# SparkFun_QwiicBus_Endpoint.net
KiCad netlist of a schematic drawn in EAGLE
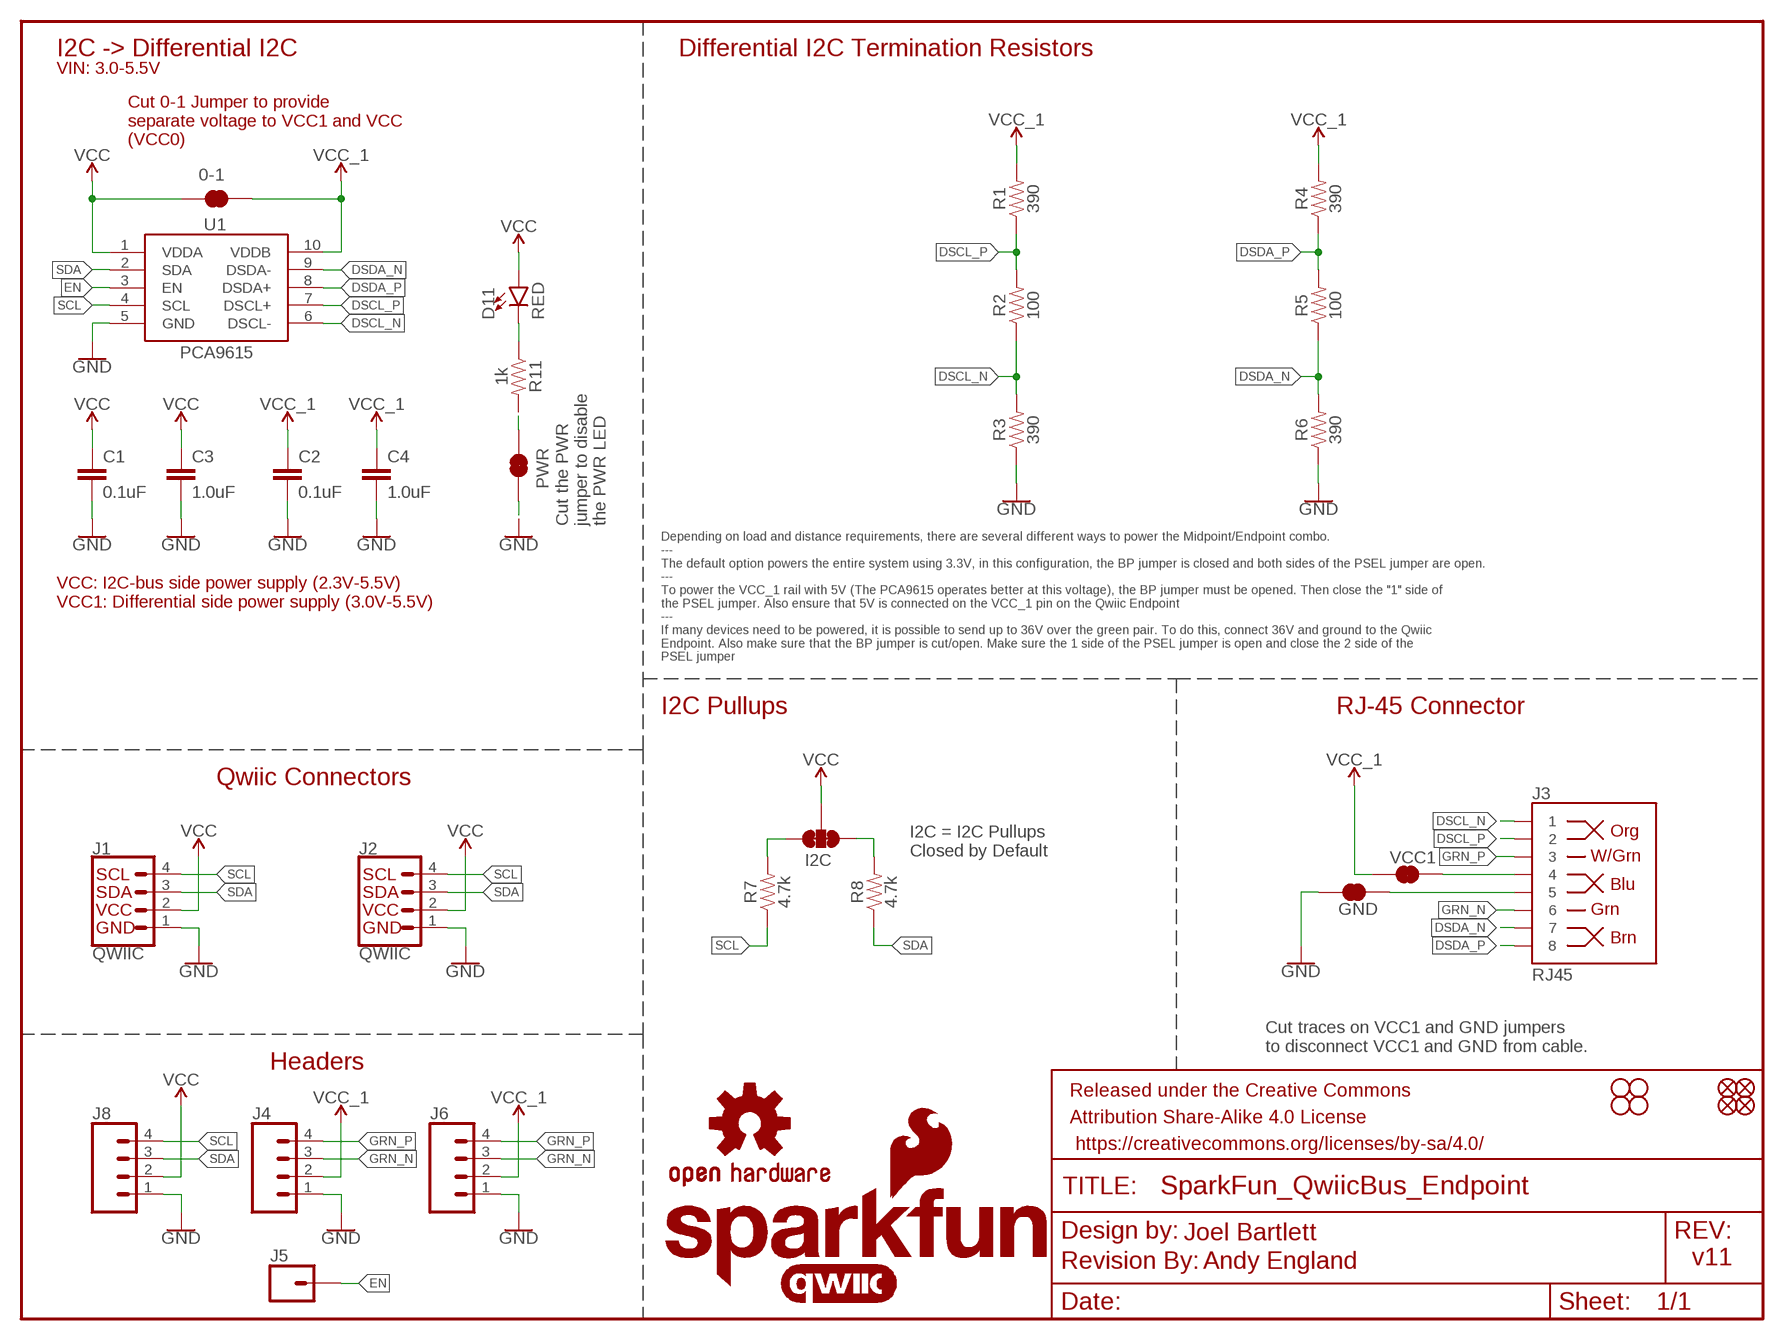
[diagram p0: schematic, sheet 1]

(export (version "E")
  (design (tool "Eeschema 10.0.6"))
  (components
    (comp (ref "0-1")
      (value "JUMPER-SMT_2_NC_TRACE_SILK")
      (footprint "eagle-import:SMT-JUMPER_2_NC_TRACE_SILK")
      (libsource (lib "eagle-import") (part "JUMPER-SMT_2_NC_TRACE_SILK"))
    )
    (comp (ref "C1")
      (value "0.1uF")
      (footprint "eagle-import:0603")
      (libsource (lib "eagle-import") (part "0.1UF-0603-25V-(+80/-20%)"))
    )
    (comp (ref "C2")
      (value "0.1uF")
      (footprint "eagle-import:0603")
      (libsource (lib "eagle-import") (part "0.1UF-0603-25V-(+80/-20%)"))
    )
    (comp (ref "C3")
      (value "1.0uF")
      (footprint "eagle-import:0603")
      (libsource (lib "eagle-import") (part "1.0UF-0603-16V-10%"))
    )
    (comp (ref "C4")
      (value "1.0uF")
      (footprint "eagle-import:0603")
      (libsource (lib "eagle-import") (part "1.0UF-0603-16V-10%"))
    )
    (comp (ref "D11")
      (value "RED")
      (footprint "eagle-import:LED-0603")
      (libsource (lib "eagle-import") (part "LED-RED0603"))
    )
    (comp (ref "FD1")
      (value "FIDUCIALUFIDUCIAL")
      (footprint "eagle-import:FIDUCIAL-MICRO")
      (libsource (lib "eagle-import") (part "FIDUCIALUFIDUCIAL"))
    )
    (comp (ref "FD2")
      (value "FIDUCIALUFIDUCIAL")
      (footprint "eagle-import:FIDUCIAL-MICRO")
      (libsource (lib "eagle-import") (part "FIDUCIALUFIDUCIAL"))
    )
    (comp (ref "FD3")
      (value "FIDUCIALUFIDUCIAL")
      (footprint "eagle-import:FIDUCIAL-MICRO")
      (libsource (lib "eagle-import") (part "FIDUCIALUFIDUCIAL"))
    )
    (comp (ref "FD4")
      (value "FIDUCIALUFIDUCIAL")
      (footprint "eagle-import:FIDUCIAL-MICRO")
      (libsource (lib "eagle-import") (part "FIDUCIALUFIDUCIAL"))
    )
    (comp (ref "FRAME1")
      (value "FRAME-LETTER")
      (footprint "eagle-import:CREATIVE_COMMONS")
      (libsource (lib "eagle-import") (part "FRAME-LETTER"))
    )
    (comp (ref "GND")
      (value "JUMPER-SMT_2_NC_TRACE_SILK")
      (footprint "eagle-import:SMT-JUMPER_2_NC_TRACE_SILK")
      (libsource (lib "eagle-import") (part "JUMPER-SMT_2_NC_TRACE_SILK"))
    )
    (comp (ref "H1")
      (value "STAND-OFF")
      (footprint "eagle-import:STAND-OFF")
      (libsource (lib "eagle-import") (part "STAND-OFF"))
    )
    (comp (ref "H2")
      (value "STAND-OFF")
      (footprint "eagle-import:STAND-OFF")
      (libsource (lib "eagle-import") (part "STAND-OFF"))
    )
    (comp (ref "H3")
      (value "STAND-OFF")
      (footprint "eagle-import:STAND-OFF")
      (libsource (lib "eagle-import") (part "STAND-OFF"))
    )
    (comp (ref "H4")
      (value "STAND-OFF")
      (footprint "eagle-import:STAND-OFF")
      (libsource (lib "eagle-import") (part "STAND-OFF"))
    )
    (comp (ref "I2C")
      (value "JUMPER-SMT_3_2-NC_TRACE_SILK")
      (footprint "eagle-import:SMT-JUMPER_3_2-NC_TRACE_SILK")
      (libsource (lib "eagle-import") (part "JUMPER-SMT_3_2-NC_TRACE_SILK"))
    )
    (comp (ref "J1")
      (value "QWIIC")
      (footprint "eagle-import:JST04_1MM_RA")
      (libsource (lib "eagle-import") (part "QWIIC_CONNECTORJS-1MM"))
    )
    (comp (ref "J2")
      (value "QWIIC")
      (footprint "eagle-import:JST04_1MM_RA")
      (libsource (lib "eagle-import") (part "QWIIC_CONNECTORJS-1MM"))
    )
    (comp (ref "J3")
      (value "RJ45")
      (footprint "eagle-import:RJ45-8")
      (libsource (lib "eagle-import") (part "RJ45-8"))
    )
    (comp (ref "J4")
      (value "CONN_041X04_NO_SILK")
      (footprint "eagle-import:1X04_NO_SILK")
      (libsource (lib "eagle-import") (part "CONN_041X04_NO_SILK"))
    )
    (comp (ref "J5")
      (value "CONN_01PTH_NO_SILK_YES_STOP")
      (footprint "eagle-import:1X01_NO_SILK")
      (libsource (lib "eagle-import") (part "CONN_01PTH_NO_SILK_YES_STOP"))
    )
    (comp (ref "J6")
      (value "CONN_041X04_NO_SILK")
      (footprint "eagle-import:1X04_NO_SILK")
      (libsource (lib "eagle-import") (part "CONN_041X04_NO_SILK"))
    )
    (comp (ref "J8")
      (value "CONN_041X04_NO_SILK")
      (footprint "eagle-import:1X04_NO_SILK")
      (libsource (lib "eagle-import") (part "CONN_041X04_NO_SILK"))
    )
    (comp (ref "LOGO1")
      (value "OSHW-LOGOM")
      (footprint "eagle-import:OSHW-LOGO-M")
      (libsource (lib "eagle-import") (part "OSHW-LOGOM"))
    )
    (comp (ref "LOGO2")
      (value "REVISION")
      (footprint "eagle-import:REVISION")
      (libsource (lib "eagle-import") (part "REVISION"))
    )
    (comp (ref "LOGO3")
      (value "QWIIC_LOGO_4MM")
      (footprint "eagle-import:QWIIC_4MM")
      (libsource (lib "eagle-import") (part "QWIIC_LOGO_4MM"))
    )
    (comp (ref "LOGO4")
      (value "SFE_LOGO_NAME_FLAME.1_INCH")
      (footprint "eagle-import:SFE_LOGO_NAME_FLAME_.1")
      (libsource (lib "eagle-import") (part "SFE_LOGO_NAME_FLAME.1_INCH"))
    )
    (comp (ref "LOGO5")
      (value "SFE_LOGO_FLAME.1_INCH")
      (footprint "eagle-import:SFE_LOGO_FLAME_.1")
      (libsource (lib "eagle-import") (part "SFE_LOGO_FLAME.1_INCH"))
    )
    (comp (ref "PWR")
      (value "JUMPER-SMT_2_NC_TRACE_SILK")
      (footprint "eagle-import:SMT-JUMPER_2_NC_TRACE_SILK")
      (libsource (lib "eagle-import") (part "JUMPER-SMT_2_NC_TRACE_SILK"))
    )
    (comp (ref "R1")
      (value "390")
      (footprint "eagle-import:0603")
      (libsource (lib "eagle-import") (part "390OHM-0603-1/10W-1%"))
    )
    (comp (ref "R2")
      (value "100")
      (footprint "eagle-import:0603")
      (libsource (lib "eagle-import") (part "100OHM-0603-1/10W-1%"))
    )
    (comp (ref "R3")
      (value "390")
      (footprint "eagle-import:0603")
      (libsource (lib "eagle-import") (part "390OHM-0603-1/10W-1%"))
    )
    (comp (ref "R4")
      (value "390")
      (footprint "eagle-import:0603")
      (libsource (lib "eagle-import") (part "390OHM-0603-1/10W-1%"))
    )
    (comp (ref "R5")
      (value "100")
      (footprint "eagle-import:0603")
      (libsource (lib "eagle-import") (part "100OHM-0603-1/10W-1%"))
    )
    (comp (ref "R6")
      (value "390")
      (footprint "eagle-import:0603")
      (libsource (lib "eagle-import") (part "390OHM-0603-1/10W-1%"))
    )
    (comp (ref "R7")
      (value "4.7k")
      (footprint "eagle-import:0603")
      (libsource (lib "eagle-import") (part "4.7KOHM-0603-1/10W-1%"))
    )
    (comp (ref "R8")
      (value "4.7k")
      (footprint "eagle-import:0603")
      (libsource (lib "eagle-import") (part "4.7KOHM-0603-1/10W-1%"))
    )
    (comp (ref "R11")
      (value "1k")
      (footprint "eagle-import:0603")
      (libsource (lib "eagle-import") (part "1KOHM-0603-1/10W-1%"))
    )
    (comp (ref "U1")
      (value "PCA9615")
      (footprint "eagle-import:TSSOP10")
      (libsource (lib "eagle-import") (part "PCA9615"))
    )
    (comp (ref "VCC1")
      (value "JUMPER-SMT_2_NC_TRACE_SILK")
      (footprint "eagle-import:SMT-JUMPER_2_NC_TRACE_SILK")
      (libsource (lib "eagle-import") (part "JUMPER-SMT_2_NC_TRACE_SILK"))
    )
  )
  (nets
    (net (code "1") (name "DSCL_N") (class "Default")
      (node (ref "J3") (pin "1") (pinfunction "1_1") (pintype "bidirectional"))
      (node (ref "R2") (pin "1") (pinfunction "1_1") (pintype "passive"))
      (node (ref "R3") (pin "2") (pinfunction "2_2") (pintype "passive"))
      (node (ref "U1") (pin "6") (pinfunction "DSCL-_6") (pintype "bidirectional"))
    )
    (net (code "2") (name "DSCL_P") (class "Default")
      (node (ref "J3") (pin "2") (pinfunction "2_2") (pintype "bidirectional"))
      (node (ref "R1") (pin "1") (pinfunction "1_1") (pintype "passive"))
      (node (ref "R2") (pin "2") (pinfunction "2_2") (pintype "passive"))
      (node (ref "U1") (pin "7") (pinfunction "DSCL+_7") (pintype "bidirectional"))
    )
    (net (code "3") (name "DSDA_N") (class "Default")
      (node (ref "J3") (pin "7") (pinfunction "7_7") (pintype "bidirectional"))
      (node (ref "R5") (pin "1") (pinfunction "1_1") (pintype "passive"))
      (node (ref "R6") (pin "2") (pinfunction "2_2") (pintype "passive"))
      (node (ref "U1") (pin "9") (pinfunction "DSDA-_9") (pintype "bidirectional"))
    )
    (net (code "4") (name "DSDA_P") (class "Default")
      (node (ref "J3") (pin "8") (pinfunction "8_8") (pintype "bidirectional"))
      (node (ref "R4") (pin "1") (pinfunction "1_1") (pintype "passive"))
      (node (ref "R5") (pin "2") (pinfunction "2_2") (pintype "passive"))
      (node (ref "U1") (pin "8") (pinfunction "DSDA+_8") (pintype "bidirectional"))
    )
    (net (code "5") (name "EN") (class "Default")
      (node (ref "J5") (pin "1") (pinfunction "1_1") (pintype "passive"))
      (node (ref "U1") (pin "3") (pinfunction "EN_3") (pintype "bidirectional"))
    )
    (net (code "6") (name "GND") (class "Default")
      (node (ref "C1") (pin "2") (pinfunction "2_2") (pintype "passive"))
      (node (ref "C2") (pin "2") (pinfunction "2_2") (pintype "passive"))
      (node (ref "C3") (pin "2") (pinfunction "2_2") (pintype "passive"))
      (node (ref "C4") (pin "2") (pinfunction "2_2") (pintype "passive"))
      (node (ref "GND") (pin "1") (pinfunction "1_1") (pintype "passive"))
      (node (ref "J1") (pin "1") (pinfunction "1_1") (pintype "power_in"))
      (node (ref "J2") (pin "1") (pinfunction "1_1") (pintype "power_in"))
      (node (ref "J4") (pin "1") (pinfunction "1_1") (pintype "passive"))
      (node (ref "J6") (pin "1") (pinfunction "1_1") (pintype "passive"))
      (node (ref "J8") (pin "1") (pinfunction "1_1") (pintype "passive"))
      (node (ref "PWR") (pin "1") (pinfunction "1_1") (pintype "passive"))
      (node (ref "R3") (pin "1") (pinfunction "1_1") (pintype "passive"))
      (node (ref "R6") (pin "1") (pinfunction "1_1") (pintype "passive"))
      (node (ref "U1") (pin "5") (pinfunction "GND_5") (pintype "bidirectional"))
    )
    (net (code "7") (name "GRN_N") (class "Default")
      (node (ref "J3") (pin "6") (pinfunction "6_6") (pintype "bidirectional"))
      (node (ref "J4") (pin "3") (pinfunction "3_3") (pintype "passive"))
      (node (ref "J6") (pin "3") (pinfunction "3_3") (pintype "passive"))
    )
    (net (code "8") (name "GRN_P") (class "Default")
      (node (ref "J3") (pin "3") (pinfunction "3_3") (pintype "bidirectional"))
      (node (ref "J4") (pin "4") (pinfunction "4_4") (pintype "passive"))
      (node (ref "J6") (pin "4") (pinfunction "4_4") (pintype "passive"))
    )
    (net (code "9") (name "Net-(D11-PadC)") (class "Default")
      (node (ref "D11") (pin "C") (pinfunction "C_C") (pintype "passive"))
      (node (ref "R11") (pin "1") (pinfunction "1_1") (pintype "passive"))
    )
    (net (code "10") (name "Net-(GND-Pad2)") (class "Default")
      (node (ref "GND") (pin "2") (pinfunction "2_2") (pintype "passive"))
      (node (ref "J3") (pin "5") (pinfunction "5_5") (pintype "bidirectional"))
    )
    (net (code "11") (name "Net-(I2C-Pad1)") (class "Default")
      (node (ref "I2C") (pin "1") (pinfunction "1_1") (pintype "passive"))
      (node (ref "R8") (pin "2") (pinfunction "2_2") (pintype "passive"))
    )
    (net (code "12") (name "Net-(I2C-Pad3)") (class "Default")
      (node (ref "I2C") (pin "3") (pinfunction "3_3") (pintype "passive"))
      (node (ref "R7") (pin "2") (pinfunction "2_2") (pintype "passive"))
    )
    (net (code "13") (name "Net-(J3-Pad4)") (class "Default")
      (node (ref "J3") (pin "4") (pinfunction "4_4") (pintype "bidirectional"))
      (node (ref "VCC1") (pin "2") (pinfunction "2_2") (pintype "passive"))
    )
    (net (code "14") (name "Net-(PWR-Pad2)") (class "Default")
      (node (ref "PWR") (pin "2") (pinfunction "2_2") (pintype "passive"))
      (node (ref "R11") (pin "2") (pinfunction "2_2") (pintype "passive"))
    )
    (net (code "15") (name "SCL") (class "Default")
      (node (ref "J1") (pin "4") (pinfunction "4_4") (pintype "passive"))
      (node (ref "J2") (pin "4") (pinfunction "4_4") (pintype "passive"))
      (node (ref "J8") (pin "4") (pinfunction "4_4") (pintype "passive"))
      (node (ref "R7") (pin "1") (pinfunction "1_1") (pintype "passive"))
      (node (ref "U1") (pin "4") (pinfunction "SCL_4") (pintype "bidirectional"))
    )
    (net (code "16") (name "SDA") (class "Default")
      (node (ref "J1") (pin "3") (pinfunction "3_3") (pintype "passive"))
      (node (ref "J2") (pin "3") (pinfunction "3_3") (pintype "passive"))
      (node (ref "J8") (pin "3") (pinfunction "3_3") (pintype "passive"))
      (node (ref "R8") (pin "1") (pinfunction "1_1") (pintype "passive"))
      (node (ref "U1") (pin "2") (pinfunction "SDA_2") (pintype "bidirectional"))
    )
    (net (code "17") (name "VCC") (class "Default")
      (node (ref "0-1") (pin "2") (pinfunction "2_2") (pintype "passive"))
      (node (ref "C1") (pin "1") (pinfunction "1_1") (pintype "passive"))
      (node (ref "C3") (pin "1") (pinfunction "1_1") (pintype "passive"))
      (node (ref "D11") (pin "A") (pinfunction "A_A") (pintype "passive"))
      (node (ref "I2C") (pin "2") (pinfunction "2_2") (pintype "passive"))
      (node (ref "J1") (pin "2") (pinfunction "2_2") (pintype "power_in"))
      (node (ref "J2") (pin "2") (pinfunction "2_2") (pintype "power_in"))
      (node (ref "J8") (pin "2") (pinfunction "2_2") (pintype "passive"))
      (node (ref "U1") (pin "1") (pinfunction "VDDA_1") (pintype "bidirectional"))
    )
    (net (code "18") (name "VCC_1") (class "Default")
      (node (ref "0-1") (pin "1") (pinfunction "1_1") (pintype "passive"))
      (node (ref "C2") (pin "1") (pinfunction "1_1") (pintype "passive"))
      (node (ref "C4") (pin "1") (pinfunction "1_1") (pintype "passive"))
      (node (ref "J4") (pin "2") (pinfunction "2_2") (pintype "passive"))
      (node (ref "J6") (pin "2") (pinfunction "2_2") (pintype "passive"))
      (node (ref "R1") (pin "2") (pinfunction "2_2") (pintype "passive"))
      (node (ref "R4") (pin "2") (pinfunction "2_2") (pintype "passive"))
      (node (ref "U1") (pin "10") (pinfunction "VDDB_10") (pintype "bidirectional"))
      (node (ref "VCC1") (pin "1") (pinfunction "1_1") (pintype "passive"))
    )
  )
)
